# MI0283QT_v10.net
KiCad netlist of a schematic drawn in EAGLE
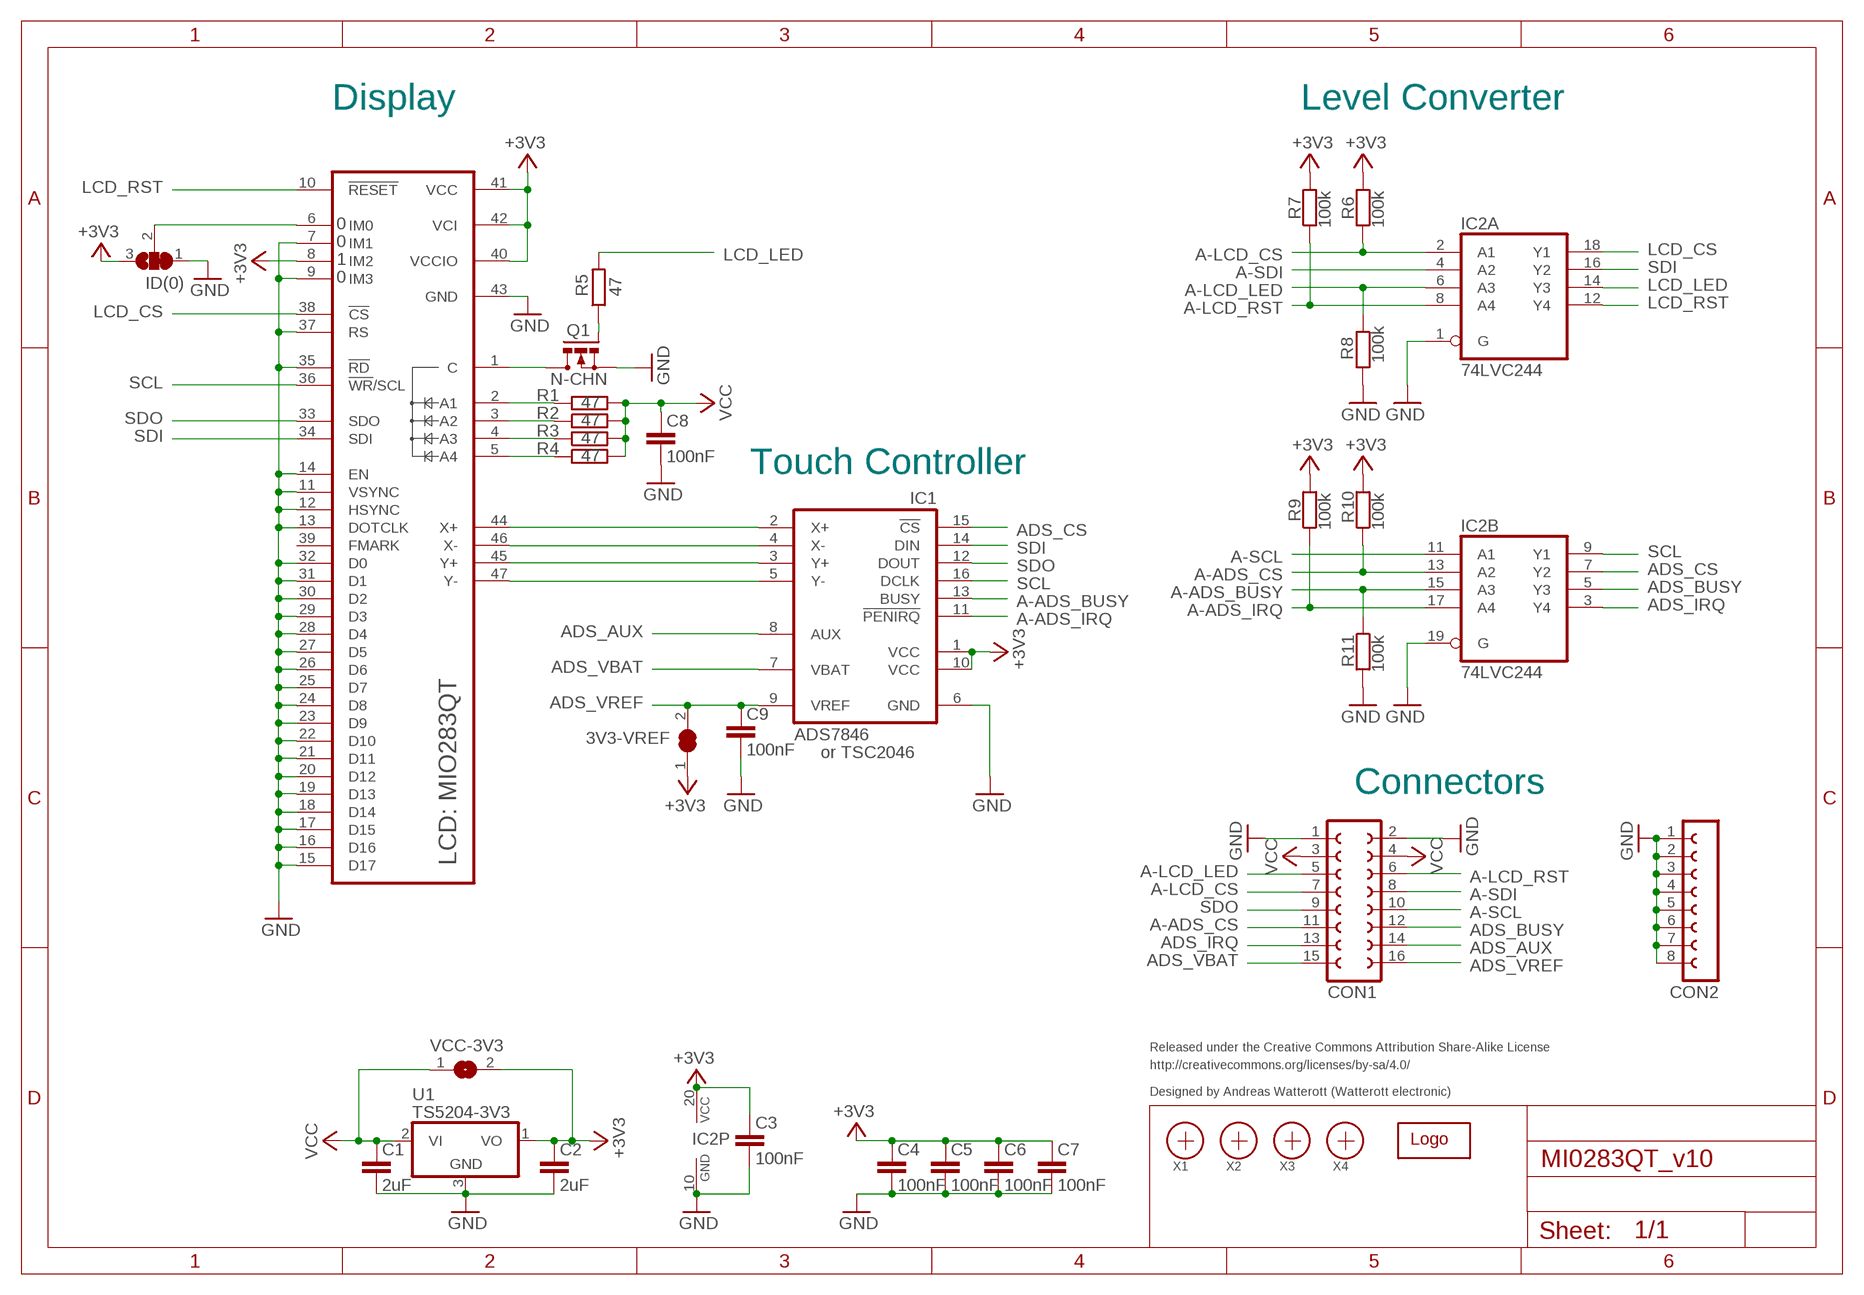
[diagram p0: schematic, sheet 1]

(export (version "E")
  (design (tool "Eeschema 10.0.6"))
  (components
    (comp (ref "3V3-VREF")
      (value "SJ")
      (footprint "eagle-import:SJ")
      (libsource (lib "eagle-import") (part "SJ"))
    )
    (comp (ref "C1")
      (value "2uF")
      (footprint "eagle-import:C0805")
      (libsource (lib "eagle-import") (part "C-EUC0805"))
    )
    (comp (ref "C2")
      (value "2uF")
      (footprint "eagle-import:C0805")
      (libsource (lib "eagle-import") (part "C-EUC0805"))
    )
    (comp (ref "C3")
      (value "100nF")
      (footprint "eagle-import:C0603")
      (libsource (lib "eagle-import") (part "C-EUC0603"))
    )
    (comp (ref "C4")
      (value "100nF")
      (footprint "eagle-import:C0603")
      (libsource (lib "eagle-import") (part "C-EUC0603"))
    )
    (comp (ref "C5")
      (value "100nF")
      (footprint "eagle-import:C0603")
      (libsource (lib "eagle-import") (part "C-EUC0603"))
    )
    (comp (ref "C6")
      (value "100nF")
      (footprint "eagle-import:C0603")
      (libsource (lib "eagle-import") (part "C-EUC0603"))
    )
    (comp (ref "C7")
      (value "100nF")
      (footprint "eagle-import:C0603")
      (libsource (lib "eagle-import") (part "C-EUC0603"))
    )
    (comp (ref "C8")
      (value "100nF")
      (footprint "eagle-import:C0603")
      (libsource (lib "eagle-import") (part "C-EUC0603"))
    )
    (comp (ref "C9")
      (value "100nF")
      (footprint "eagle-import:C0603")
      (libsource (lib "eagle-import") (part "C-EUC0603"))
    )
    (comp (ref "CON1")
      (value "FE08-2")
      (footprint "eagle-import:FE08-2")
      (libsource (lib "eagle-import") (part "FE08-2"))
    )
    (comp (ref "CON2")
      (value "FE08-1")
      (footprint "eagle-import:FE08")
      (libsource (lib "eagle-import") (part "FE08-1"))
    )
    (comp (ref "IC1")
      (value "ADS7846")
      (footprint "eagle-import:SSOP16")
      (libsource (lib "eagle-import") (part "ADS7846"))
    )
    (comp (ref "IC2")
      (value "74LVC244")
      (footprint "eagle-import:SO20W")
      (libsource (lib "eagle-import") (part "74244DWHC"))
    )
    (comp (ref "ID(0)")
      (value "SJ2W")
      (footprint "eagle-import:SJ_2")
      (libsource (lib "eagle-import") (part "SJ2W"))
    )
    (comp (ref "LCD")
      (value "MI0283QT")
      (footprint "eagle-import:MI0283QT")
      (libsource (lib "eagle-import") (part "MI0283QT"))
    )
    (comp (ref "Q1")
      (value "N-CHN")
      (footprint "eagle-import:MICRO3")
      (libsource (lib "eagle-import") (part "IRLML2502"))
    )
    (comp (ref "R1")
      (value "47")
      (footprint "eagle-import:R0603")
      (libsource (lib "eagle-import") (part "R-EU_R0603"))
    )
    (comp (ref "R2")
      (value "47")
      (footprint "eagle-import:R0603")
      (libsource (lib "eagle-import") (part "R-EU_R0603"))
    )
    (comp (ref "R3")
      (value "47")
      (footprint "eagle-import:R0603")
      (libsource (lib "eagle-import") (part "R-EU_R0603"))
    )
    (comp (ref "R4")
      (value "47")
      (footprint "eagle-import:R0603")
      (libsource (lib "eagle-import") (part "R-EU_R0603"))
    )
    (comp (ref "R5")
      (value "47")
      (footprint "eagle-import:R0603")
      (libsource (lib "eagle-import") (part "R-EU_R0603"))
    )
    (comp (ref "R6")
      (value "100k")
      (footprint "eagle-import:R0603")
      (libsource (lib "eagle-import") (part "R-EU_R0603"))
    )
    (comp (ref "R7")
      (value "100k")
      (footprint "eagle-import:R0603")
      (libsource (lib "eagle-import") (part "R-EU_R0603"))
    )
    (comp (ref "R8")
      (value "100k")
      (footprint "eagle-import:R0603")
      (libsource (lib "eagle-import") (part "R-EU_R0603"))
    )
    (comp (ref "R9")
      (value "100k")
      (footprint "eagle-import:R0603")
      (libsource (lib "eagle-import") (part "R-EU_R0603"))
    )
    (comp (ref "R10")
      (value "100k")
      (footprint "eagle-import:R0603")
      (libsource (lib "eagle-import") (part "R-EU_R0603"))
    )
    (comp (ref "R11")
      (value "100k")
      (footprint "eagle-import:R0603")
      (libsource (lib "eagle-import") (part "R-EU_R0603"))
    )
    (comp (ref "U$1")
      (value "WE-LOGO")
      (footprint "eagle-import:WE-LOGO")
      (libsource (lib "eagle-import") (part "WE-LOGO"))
    )
    (comp (ref "U1")
      (value "TS5204-3V3")
      (footprint "eagle-import:SOT23")
      (libsource (lib "eagle-import") (part "TS5204"))
    )
    (comp (ref "VCC-3V3")
      (value "SJ")
      (footprint "eagle-import:SJ")
      (libsource (lib "eagle-import") (part "SJ"))
    )
    (comp (ref "X1")
      (value "PASSER")
      (footprint "eagle-import:PASSER")
      (libsource (lib "eagle-import") (part "PASSER"))
    )
    (comp (ref "X2")
      (value "PASSER")
      (footprint "eagle-import:PASSER")
      (libsource (lib "eagle-import") (part "PASSER"))
    )
    (comp (ref "X3")
      (value "PASSER")
      (footprint "eagle-import:PASSER")
      (libsource (lib "eagle-import") (part "PASSER"))
    )
    (comp (ref "X4")
      (value "PASSER")
      (footprint "eagle-import:PASSER")
      (libsource (lib "eagle-import") (part "PASSER"))
    )
  )
  (nets
    (net (code "1") (name "+3V3") (class "Default")
      (node (ref "3V3-VREF") (pin "1") (pinfunction "1_1") (pintype "passive"))
      (node (ref "C2") (pin "1") (pinfunction "1_1") (pintype "passive"))
      (node (ref "C3") (pin "1") (pinfunction "1_1") (pintype "passive"))
      (node (ref "C4") (pin "1") (pinfunction "1_1") (pintype "passive"))
      (node (ref "C5") (pin "1") (pinfunction "1_1") (pintype "passive"))
      (node (ref "C6") (pin "1") (pinfunction "1_1") (pintype "passive"))
      (node (ref "C7") (pin "1") (pinfunction "1_1") (pintype "passive"))
      (node (ref "IC1") (pin "1") (pinfunction "VCC_1") (pintype "power_in"))
      (node (ref "IC1") (pin "10") (pinfunction "VCC_10") (pintype "power_in"))
      (node (ref "IC2") (pin "20") (pinfunction "VCC_20") (pintype "power_in"))
      (node (ref "ID(0)") (pin "3") (pinfunction "3_3") (pintype "passive"))
      (node (ref "LCD") (pin "40") (pinfunction "VCCIO_40") (pintype "power_in"))
      (node (ref "LCD") (pin "41") (pinfunction "VCC_41") (pintype "power_in"))
      (node (ref "LCD") (pin "42") (pinfunction "VCI_42") (pintype "power_in"))
      (node (ref "LCD") (pin "8") (pinfunction "IM2_8") (pintype "input"))
      (node (ref "R10") (pin "2") (pinfunction "2_2") (pintype "passive"))
      (node (ref "R6") (pin "2") (pinfunction "2_2") (pintype "passive"))
      (node (ref "R7") (pin "2") (pinfunction "2_2") (pintype "passive"))
      (node (ref "R9") (pin "2") (pinfunction "2_2") (pintype "passive"))
      (node (ref "U1") (pin "1") (pinfunction "VO_1") (pintype "passive"))
      (node (ref "VCC-3V3") (pin "2") (pinfunction "2_2") (pintype "passive"))
    )
    (net (code "2") (name "/A-ADS_BUSY") (class "Default")
      (node (ref "IC1") (pin "13") (pinfunction "BUSY_13") (pintype "output"))
      (node (ref "IC2") (pin "15") (pinfunction "A3_15") (pintype "input"))
      (node (ref "R11") (pin "1") (pinfunction "1_1") (pintype "passive"))
    )
    (net (code "3") (name "/A-ADS_CS") (class "Default")
      (node (ref "CON1") (pin "11") (pinfunction "11_11") (pintype "passive"))
      (node (ref "IC2") (pin "13") (pinfunction "A2_13") (pintype "input"))
      (node (ref "R10") (pin "1") (pinfunction "1_1") (pintype "passive"))
    )
    (net (code "4") (name "/A-ADS_IRQ") (class "Default")
      (node (ref "IC1") (pin "11") (pinfunction "~{PENIRQ}_11") (pintype "output"))
      (node (ref "IC2") (pin "17") (pinfunction "A4_17") (pintype "input"))
      (node (ref "R9") (pin "1") (pinfunction "1_1") (pintype "passive"))
    )
    (net (code "5") (name "/A-LCD_CS") (class "Default")
      (node (ref "CON1") (pin "7") (pinfunction "7_7") (pintype "passive"))
      (node (ref "IC2") (pin "2") (pinfunction "A1_2") (pintype "input"))
      (node (ref "R6") (pin "1") (pinfunction "1_1") (pintype "passive"))
    )
    (net (code "6") (name "/A-LCD_LED") (class "Default")
      (node (ref "CON1") (pin "5") (pinfunction "5_5") (pintype "passive"))
      (node (ref "IC2") (pin "6") (pinfunction "A3_6") (pintype "input"))
      (node (ref "R8") (pin "1") (pinfunction "1_1") (pintype "passive"))
    )
    (net (code "7") (name "/A-LCD_RST") (class "Default")
      (node (ref "CON1") (pin "6") (pinfunction "6_6") (pintype "passive"))
      (node (ref "IC2") (pin "8") (pinfunction "A4_8") (pintype "input"))
      (node (ref "R7") (pin "1") (pinfunction "1_1") (pintype "passive"))
    )
    (net (code "8") (name "/A-SCL") (class "Default")
      (node (ref "CON1") (pin "10") (pinfunction "10_10") (pintype "passive"))
      (node (ref "IC2") (pin "11") (pinfunction "A1_11") (pintype "input"))
    )
    (net (code "9") (name "/A-SDI") (class "Default")
      (node (ref "CON1") (pin "8") (pinfunction "8_8") (pintype "passive"))
      (node (ref "IC2") (pin "4") (pinfunction "A2_4") (pintype "input"))
    )
    (net (code "10") (name "/ADS_AUX") (class "Default")
      (node (ref "CON1") (pin "14") (pinfunction "14_14") (pintype "passive"))
      (node (ref "IC1") (pin "8") (pinfunction "AUX_8") (pintype "input"))
    )
    (net (code "11") (name "/ADS_BUSY") (class "Default")
      (node (ref "CON1") (pin "12") (pinfunction "12_12") (pintype "passive"))
      (node (ref "IC2") (pin "5") (pinfunction "Y3_5") (pintype "tri_state"))
    )
    (net (code "12") (name "/ADS_CS") (class "Default")
      (node (ref "IC1") (pin "15") (pinfunction "~{CS}_15") (pintype "input"))
      (node (ref "IC2") (pin "7") (pinfunction "Y2_7") (pintype "tri_state"))
    )
    (net (code "13") (name "/ADS_IRQ") (class "Default")
      (node (ref "CON1") (pin "13") (pinfunction "13_13") (pintype "passive"))
      (node (ref "IC2") (pin "3") (pinfunction "Y4_3") (pintype "tri_state"))
    )
    (net (code "14") (name "/ADS_VBAT") (class "Default")
      (node (ref "CON1") (pin "15") (pinfunction "15_15") (pintype "passive"))
      (node (ref "IC1") (pin "7") (pinfunction "VBAT_7") (pintype "input"))
    )
    (net (code "15") (name "/ADS_VREF") (class "Default")
      (node (ref "3V3-VREF") (pin "2") (pinfunction "2_2") (pintype "passive"))
      (node (ref "C9") (pin "1") (pinfunction "1_1") (pintype "passive"))
      (node (ref "CON1") (pin "16") (pinfunction "16_16") (pintype "passive"))
      (node (ref "IC1") (pin "9") (pinfunction "VREF_9") (pintype "bidirectional"))
    )
    (net (code "16") (name "/LCD_CS") (class "Default")
      (node (ref "IC2") (pin "18") (pinfunction "Y1_18") (pintype "tri_state"))
      (node (ref "LCD") (pin "38") (pinfunction "~{CS}_38") (pintype "input"))
    )
    (net (code "17") (name "/LCD_LED") (class "Default")
      (node (ref "IC2") (pin "14") (pinfunction "Y3_14") (pintype "tri_state"))
      (node (ref "R5") (pin "2") (pinfunction "2_2") (pintype "passive"))
    )
    (net (code "18") (name "/LCD_RST") (class "Default")
      (node (ref "IC2") (pin "12") (pinfunction "Y4_12") (pintype "tri_state"))
      (node (ref "LCD") (pin "10") (pinfunction "~{RESET}_10") (pintype "input"))
    )
    (net (code "19") (name "/SCL") (class "Default")
      (node (ref "IC1") (pin "16") (pinfunction "DCLK_16") (pintype "output"))
      (node (ref "IC2") (pin "9") (pinfunction "Y1_9") (pintype "tri_state"))
      (node (ref "LCD") (pin "36") (pinfunction "~{WR}/SCL_36") (pintype "input"))
    )
    (net (code "20") (name "/SDI") (class "Default")
      (node (ref "IC1") (pin "14") (pinfunction "DIN_14") (pintype "input"))
      (node (ref "IC2") (pin "16") (pinfunction "Y2_16") (pintype "tri_state"))
      (node (ref "LCD") (pin "34") (pinfunction "SDI_34") (pintype "input"))
    )
    (net (code "21") (name "/SDO") (class "Default")
      (node (ref "CON1") (pin "9") (pinfunction "9_9") (pintype "passive"))
      (node (ref "IC1") (pin "12") (pinfunction "DOUT_12") (pintype "input"))
      (node (ref "LCD") (pin "33") (pinfunction "SDO_33") (pintype "output"))
    )
    (net (code "22") (name "GND") (class "Default")
      (node (ref "C1") (pin "2") (pinfunction "2_2") (pintype "passive"))
      (node (ref "C2") (pin "2") (pinfunction "2_2") (pintype "passive"))
      (node (ref "C3") (pin "2") (pinfunction "2_2") (pintype "passive"))
      (node (ref "C4") (pin "2") (pinfunction "2_2") (pintype "passive"))
      (node (ref "C5") (pin "2") (pinfunction "2_2") (pintype "passive"))
      (node (ref "C6") (pin "2") (pinfunction "2_2") (pintype "passive"))
      (node (ref "C7") (pin "2") (pinfunction "2_2") (pintype "passive"))
      (node (ref "C8") (pin "2") (pinfunction "2_2") (pintype "passive"))
      (node (ref "C9") (pin "2") (pinfunction "2_2") (pintype "passive"))
      (node (ref "CON1") (pin "1") (pinfunction "1_1") (pintype "passive"))
      (node (ref "CON1") (pin "2") (pinfunction "2_2") (pintype "passive"))
      (node (ref "CON2") (pin "1") (pinfunction "1_1") (pintype "passive"))
      (node (ref "CON2") (pin "2") (pinfunction "2_2") (pintype "passive"))
      (node (ref "CON2") (pin "3") (pinfunction "3_3") (pintype "passive"))
      (node (ref "CON2") (pin "4") (pinfunction "4_4") (pintype "passive"))
      (node (ref "CON2") (pin "5") (pinfunction "5_5") (pintype "passive"))
      (node (ref "CON2") (pin "6") (pinfunction "6_6") (pintype "passive"))
      (node (ref "CON2") (pin "7") (pinfunction "7_7") (pintype "passive"))
      (node (ref "CON2") (pin "8") (pinfunction "8_8") (pintype "passive"))
      (node (ref "IC1") (pin "6") (pinfunction "GND_6") (pintype "power_in"))
      (node (ref "IC2") (pin "1") (pinfunction "G_1") (pintype "input"))
      (node (ref "IC2") (pin "10") (pinfunction "GND_10") (pintype "power_in"))
      (node (ref "IC2") (pin "19") (pinfunction "G_19") (pintype "input"))
      (node (ref "ID(0)") (pin "1") (pinfunction "1_1") (pintype "passive"))
      (node (ref "LCD") (pin "11") (pinfunction "VSYNC_11") (pintype "input"))
      (node (ref "LCD") (pin "12") (pinfunction "HSYNC_12") (pintype "input"))
      (node (ref "LCD") (pin "13") (pinfunction "DOTCLK_13") (pintype "input"))
      (node (ref "LCD") (pin "14") (pinfunction "EN_14") (pintype "input"))
      (node (ref "LCD") (pin "15") (pinfunction "D17_15") (pintype "input"))
      (node (ref "LCD") (pin "16") (pinfunction "D16_16") (pintype "input"))
      (node (ref "LCD") (pin "17") (pinfunction "D15_17") (pintype "input"))
      (node (ref "LCD") (pin "18") (pinfunction "D14_18") (pintype "input"))
      (node (ref "LCD") (pin "19") (pinfunction "D13_19") (pintype "input"))
      (node (ref "LCD") (pin "20") (pinfunction "D12_20") (pintype "input"))
      (node (ref "LCD") (pin "21") (pinfunction "D11_21") (pintype "input"))
      (node (ref "LCD") (pin "22") (pinfunction "D10_22") (pintype "input"))
      (node (ref "LCD") (pin "23") (pinfunction "D9_23") (pintype "input"))
      (node (ref "LCD") (pin "24") (pinfunction "D8_24") (pintype "input"))
      (node (ref "LCD") (pin "25") (pinfunction "D7_25") (pintype "input"))
      (node (ref "LCD") (pin "26") (pinfunction "D6_26") (pintype "input"))
      (node (ref "LCD") (pin "27") (pinfunction "D5_27") (pintype "input"))
      (node (ref "LCD") (pin "28") (pinfunction "D4_28") (pintype "input"))
      (node (ref "LCD") (pin "29") (pinfunction "D3_29") (pintype "input"))
      (node (ref "LCD") (pin "30") (pinfunction "D2_30") (pintype "input"))
      (node (ref "LCD") (pin "31") (pinfunction "D1_31") (pintype "input"))
      (node (ref "LCD") (pin "32") (pinfunction "D0_32") (pintype "input"))
      (node (ref "LCD") (pin "35") (pinfunction "~{RD}_35") (pintype "input"))
      (node (ref "LCD") (pin "37") (pinfunction "RS_37") (pintype "input"))
      (node (ref "LCD") (pin "43") (pinfunction "GND_43") (pintype "power_in"))
      (node (ref "LCD") (pin "7") (pinfunction "IM1_7") (pintype "input"))
      (node (ref "LCD") (pin "9") (pinfunction "IM3_9") (pintype "input"))
      (node (ref "Q1") (pin "2") (pinfunction "S_2") (pintype "passive"))
      (node (ref "R11") (pin "2") (pinfunction "2_2") (pintype "passive"))
      (node (ref "R8") (pin "2") (pinfunction "2_2") (pintype "passive"))
      (node (ref "U1") (pin "3") (pinfunction "GND_3") (pintype "passive"))
    )
    (net (code "23") (name "Net-(IC1-X+)") (class "Default")
      (node (ref "IC1") (pin "2") (pinfunction "X+_2") (pintype "input"))
      (node (ref "LCD") (pin "44") (pinfunction "X+_44") (pintype "passive"))
    )
    (net (code "24") (name "Net-(IC1-X-)") (class "Default")
      (node (ref "IC1") (pin "4") (pinfunction "X-_4") (pintype "input"))
      (node (ref "LCD") (pin "46") (pinfunction "X-_46") (pintype "passive"))
    )
    (net (code "25") (name "Net-(IC1-Y+)") (class "Default")
      (node (ref "IC1") (pin "3") (pinfunction "Y+_3") (pintype "input"))
      (node (ref "LCD") (pin "45") (pinfunction "Y+_45") (pintype "passive"))
    )
    (net (code "26") (name "Net-(IC1-Y-)") (class "Default")
      (node (ref "IC1") (pin "5") (pinfunction "Y-_5") (pintype "input"))
      (node (ref "LCD") (pin "47") (pinfunction "Y-_47") (pintype "passive"))
    )
    (net (code "27") (name "Net-(LCD-A1)") (class "Default")
      (node (ref "LCD") (pin "2") (pinfunction "A1_2") (pintype "power_in"))
      (node (ref "R1") (pin "1") (pinfunction "1_1") (pintype "passive"))
    )
    (net (code "28") (name "Net-(LCD-A2)") (class "Default")
      (node (ref "LCD") (pin "3") (pinfunction "A2_3") (pintype "power_in"))
      (node (ref "R2") (pin "1") (pinfunction "1_1") (pintype "passive"))
    )
    (net (code "29") (name "Net-(LCD-A3)") (class "Default")
      (node (ref "LCD") (pin "4") (pinfunction "A3_4") (pintype "power_in"))
      (node (ref "R3") (pin "1") (pinfunction "1_1") (pintype "passive"))
    )
    (net (code "30") (name "Net-(LCD-A4)") (class "Default")
      (node (ref "LCD") (pin "5") (pinfunction "A4_5") (pintype "power_in"))
      (node (ref "R4") (pin "1") (pinfunction "1_1") (pintype "passive"))
    )
    (net (code "31") (name "Net-(LCD-C)") (class "Default")
      (node (ref "LCD") (pin "1") (pinfunction "C_1") (pintype "power_in"))
      (node (ref "Q1") (pin "3") (pinfunction "D_3") (pintype "passive"))
    )
    (net (code "32") (name "Net-(LCD-IM0)") (class "Default")
      (node (ref "ID(0)") (pin "2") (pinfunction "2_2") (pintype "passive"))
      (node (ref "LCD") (pin "6") (pinfunction "IM0_6") (pintype "input"))
    )
    (net (code "33") (name "Net-(Q1-G)") (class "Default")
      (node (ref "Q1") (pin "1") (pinfunction "G_1") (pintype "passive"))
      (node (ref "R5") (pin "1") (pinfunction "1_1") (pintype "passive"))
    )
    (net (code "34") (name "VCC") (class "Default")
      (node (ref "C1") (pin "1") (pinfunction "1_1") (pintype "passive"))
      (node (ref "C8") (pin "1") (pinfunction "1_1") (pintype "passive"))
      (node (ref "CON1") (pin "3") (pinfunction "3_3") (pintype "passive"))
      (node (ref "CON1") (pin "4") (pinfunction "4_4") (pintype "passive"))
      (node (ref "R1") (pin "2") (pinfunction "2_2") (pintype "passive"))
      (node (ref "R2") (pin "2") (pinfunction "2_2") (pintype "passive"))
      (node (ref "R3") (pin "2") (pinfunction "2_2") (pintype "passive"))
      (node (ref "R4") (pin "2") (pinfunction "2_2") (pintype "passive"))
      (node (ref "U1") (pin "2") (pinfunction "VI_2") (pintype "input"))
      (node (ref "VCC-3V3") (pin "1") (pinfunction "1_1") (pintype "passive"))
    )
    (net (code "35") (name "unconnected-(LCD-FMARK-Pad39)") (class "Default")
      (node (ref "LCD") (pin "39") (pinfunction "FMARK_39") (pintype "output"))
    )
  )
)
